# analog_pwr.net
KiCad netlist of a schematic drawn in Altium Designer
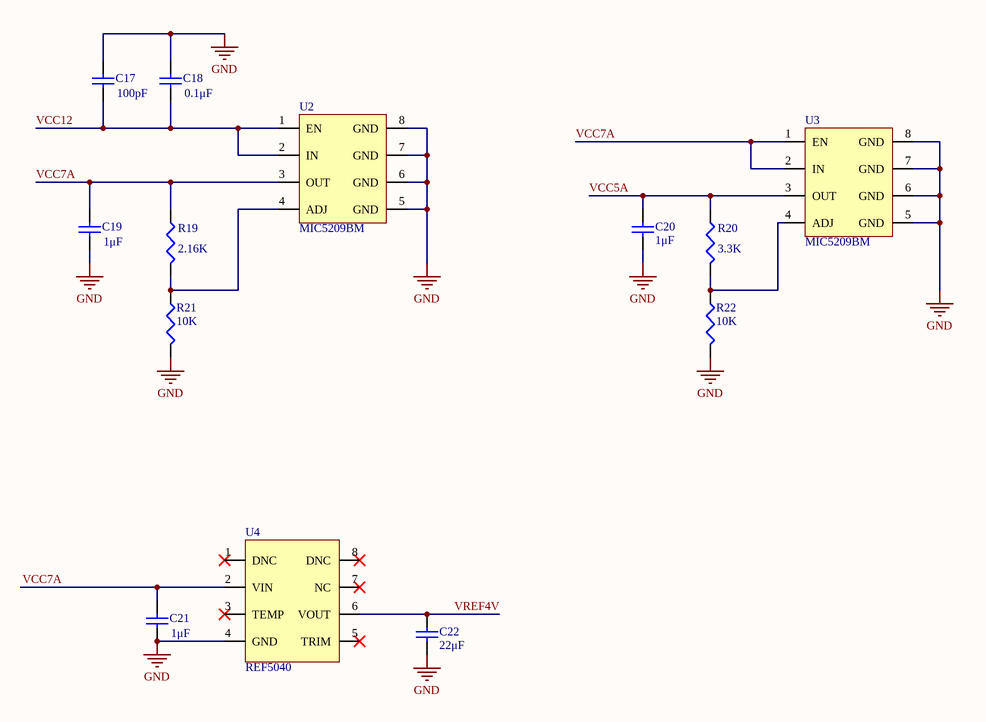
[diagram p0: analog_pwr.SchDoc]

(export (version "E")
  (design (tool "Eeschema 10.0.6"))
  (components
    (comp (ref "C17")
      (value "100pF")
      (footprint "1608[0603]")
      (description "Capacitor (Semiconductor SIM Model)")
      (fields (field (name "Comment") "Cap Semi") (field (name "PUBLISHER") "Altium Limited"))
      (libsource (lib "Miscellaneous Devices") (part "Cap Semi"))
    )
    (comp (ref "C18")
      (value "0.1μF")
      (footprint "1608[0603]")
      (description "Capacitor (Semiconductor SIM Model)")
      (fields (field (name "Comment") "Cap Semi") (field (name "PUBLISHER") "Altium Limited"))
      (libsource (lib "Miscellaneous Devices") (part "Cap Semi"))
    )
    (comp (ref "C19")
      (value "1μF")
      (footprint "1608[0603]")
      (description "Capacitor (Semiconductor SIM Model)")
      (fields (field (name "Comment") "Cap Semi") (field (name "PUBLISHER") "Altium Limited"))
      (libsource (lib "Miscellaneous Devices") (part "Cap Semi"))
    )
    (comp (ref "C20")
      (value "1μF")
      (footprint "1608[0603]")
      (description "Capacitor (Semiconductor SIM Model)")
      (fields (field (name "Comment") "Cap Semi") (field (name "PUBLISHER") "Altium Limited"))
      (libsource (lib "Miscellaneous Devices") (part "Cap Semi"))
    )
    (comp (ref "C21")
      (value "1μF")
      (footprint "1608[0603]")
      (description "Capacitor (Semiconductor SIM Model)")
      (fields (field (name "Comment") "Cap Semi") (field (name "PUBLISHER") "Altium Limited"))
      (libsource (lib "Miscellaneous Devices") (part "Cap Semi"))
    )
    (comp (ref "C22")
      (value "22μF")
      (footprint "1608[0603]")
      (description "Capacitor (Semiconductor SIM Model)")
      (fields (field (name "Comment") "Cap Semi") (field (name "PUBLISHER") "Altium Limited"))
      (libsource (lib "Miscellaneous Devices") (part "Cap Semi"))
    )
    (comp (ref "R19")
      (value "2.16K")
      (footprint "J1-0603")
      (description "Resistor")
      (fields (field (name "Comment") "Res3") (field (name "PUBLISHER") "Altium Limited"))
      (libsource (lib "Miscellaneous Devices") (part "Res3"))
    )
    (comp (ref "R20")
      (value "3.3K")
      (footprint "J1-0603")
      (description "Resistor")
      (fields (field (name "Comment") "Res3") (field (name "PUBLISHER") "Altium Limited"))
      (libsource (lib "Miscellaneous Devices") (part "Res3"))
    )
    (comp (ref "R21")
      (value "10K")
      (footprint "J1-0603")
      (description "Resistor")
      (fields (field (name "Comment") "Res3") (field (name "PUBLISHER") "Altium Limited"))
      (libsource (lib "Miscellaneous Devices") (part "Res3"))
    )
    (comp (ref "R22")
      (value "10K")
      (footprint "J1-0603")
      (description "Resistor")
      (fields (field (name "Comment") "Res3") (field (name "PUBLISHER") "Altium Limited"))
      (libsource (lib "Miscellaneous Devices") (part "Res3"))
    )
    (comp (ref "U2")
      (value "MIC5209BM")
      (footprint "SOIC127P600X175-8N")
      (libsource (lib "nir_usb") (part "MIC5209BM"))
    )
    (comp (ref "U3")
      (value "MIC5209BM")
      (footprint "SOIC127P600X175-8N")
      (libsource (lib "nir_usb") (part "MIC5209BM"))
    )
    (comp (ref "U4")
      (value "REF5040")
      (footprint "SOIC127P600X175-8N")
      (libsource (lib "nir_usb") (part "REF5040"))
    )
  )
  (nets
    (net (code "1") (name "/VCC5A") (class "Default")
      (node (ref "C20") (pin "2") (pinfunction "2_2") (pintype "passive"))
      (node (ref "R20") (pin "1") (pinfunction "1_1") (pintype "passive"))
      (node (ref "U3") (pin "3") (pinfunction "OUT_3") (pintype "passive"))
    )
    (net (code "2") (name "/VCC7A") (class "Default")
      (node (ref "C19") (pin "2") (pinfunction "2_2") (pintype "passive"))
      (node (ref "C21") (pin "2") (pinfunction "2_2") (pintype "passive"))
      (node (ref "R19") (pin "1") (pinfunction "1_1") (pintype "passive"))
      (node (ref "U2") (pin "3") (pinfunction "OUT_3") (pintype "passive"))
      (node (ref "U3") (pin "1") (pinfunction "EN_1") (pintype "passive"))
      (node (ref "U3") (pin "2") (pinfunction "IN_2") (pintype "passive"))
      (node (ref "U4") (pin "2") (pinfunction "VIN_2") (pintype "passive"))
    )
    (net (code "3") (name "/VCC12") (class "Default")
      (node (ref "C17") (pin "1") (pinfunction "1_1") (pintype "passive"))
      (node (ref "C18") (pin "1") (pinfunction "1_1") (pintype "passive"))
      (node (ref "U2") (pin "1") (pinfunction "EN_1") (pintype "passive"))
      (node (ref "U2") (pin "2") (pinfunction "IN_2") (pintype "passive"))
    )
    (net (code "4") (name "/VREF4V") (class "Default")
      (node (ref "C22") (pin "2") (pinfunction "2_2") (pintype "passive"))
      (node (ref "U4") (pin "6") (pinfunction "VOUT_6") (pintype "passive"))
    )
    (net (code "5") (name "GND") (class "Default")
      (node (ref "C17") (pin "2") (pinfunction "2_2") (pintype "passive"))
      (node (ref "C18") (pin "2") (pinfunction "2_2") (pintype "passive"))
      (node (ref "C19") (pin "1") (pinfunction "1_1") (pintype "passive"))
      (node (ref "C20") (pin "1") (pinfunction "1_1") (pintype "passive"))
      (node (ref "C21") (pin "1") (pinfunction "1_1") (pintype "passive"))
      (node (ref "C22") (pin "1") (pinfunction "1_1") (pintype "passive"))
      (node (ref "R21") (pin "2") (pinfunction "2_2") (pintype "passive"))
      (node (ref "R22") (pin "2") (pinfunction "2_2") (pintype "passive"))
      (node (ref "U2") (pin "5") (pinfunction "GND_5") (pintype "passive"))
      (node (ref "U2") (pin "6") (pinfunction "GND_6") (pintype "passive"))
      (node (ref "U2") (pin "7") (pinfunction "GND_7") (pintype "passive"))
      (node (ref "U2") (pin "8") (pinfunction "GND_8") (pintype "passive"))
      (node (ref "U3") (pin "5") (pinfunction "GND_5") (pintype "passive"))
      (node (ref "U3") (pin "6") (pinfunction "GND_6") (pintype "passive"))
      (node (ref "U3") (pin "7") (pinfunction "GND_7") (pintype "passive"))
      (node (ref "U3") (pin "8") (pinfunction "GND_8") (pintype "passive"))
      (node (ref "U4") (pin "4") (pinfunction "GND_4") (pintype "passive"))
    )
    (net (code "6") (name "Net-(U2-ADJ)") (class "Default")
      (node (ref "R19") (pin "2") (pinfunction "2_2") (pintype "passive"))
      (node (ref "R21") (pin "1") (pinfunction "1_1") (pintype "passive"))
      (node (ref "U2") (pin "4") (pinfunction "ADJ_4") (pintype "passive"))
    )
    (net (code "7") (name "Net-(U3-ADJ)") (class "Default")
      (node (ref "R20") (pin "2") (pinfunction "2_2") (pintype "passive"))
      (node (ref "R22") (pin "1") (pinfunction "1_1") (pintype "passive"))
      (node (ref "U3") (pin "4") (pinfunction "ADJ_4") (pintype "passive"))
    )
    (net (code "8") (name "unconnected-(U4-DNC-Pad1)") (class "Default")
      (node (ref "U4") (pin "1") (pinfunction "DNC_1") (pintype "passive+no_connect"))
    )
    (net (code "9") (name "unconnected-(U4-DNC-Pad8)") (class "Default")
      (node (ref "U4") (pin "8") (pinfunction "DNC_8") (pintype "passive+no_connect"))
    )
    (net (code "10") (name "unconnected-(U4-NC-Pad7)") (class "Default")
      (node (ref "U4") (pin "7") (pinfunction "NC_7") (pintype "passive+no_connect"))
    )
    (net (code "11") (name "unconnected-(U4-TEMP-Pad3)") (class "Default")
      (node (ref "U4") (pin "3") (pinfunction "TEMP_3") (pintype "passive+no_connect"))
    )
    (net (code "12") (name "unconnected-(U4-TRIM-Pad5)") (class "Default")
      (node (ref "U4") (pin "5") (pinfunction "TRIM_5") (pintype "passive+no_connect"))
    )
  )
)
